# sensors_actuators_shieldv2_0.net
KiCad netlist of a schematic drawn in EAGLE
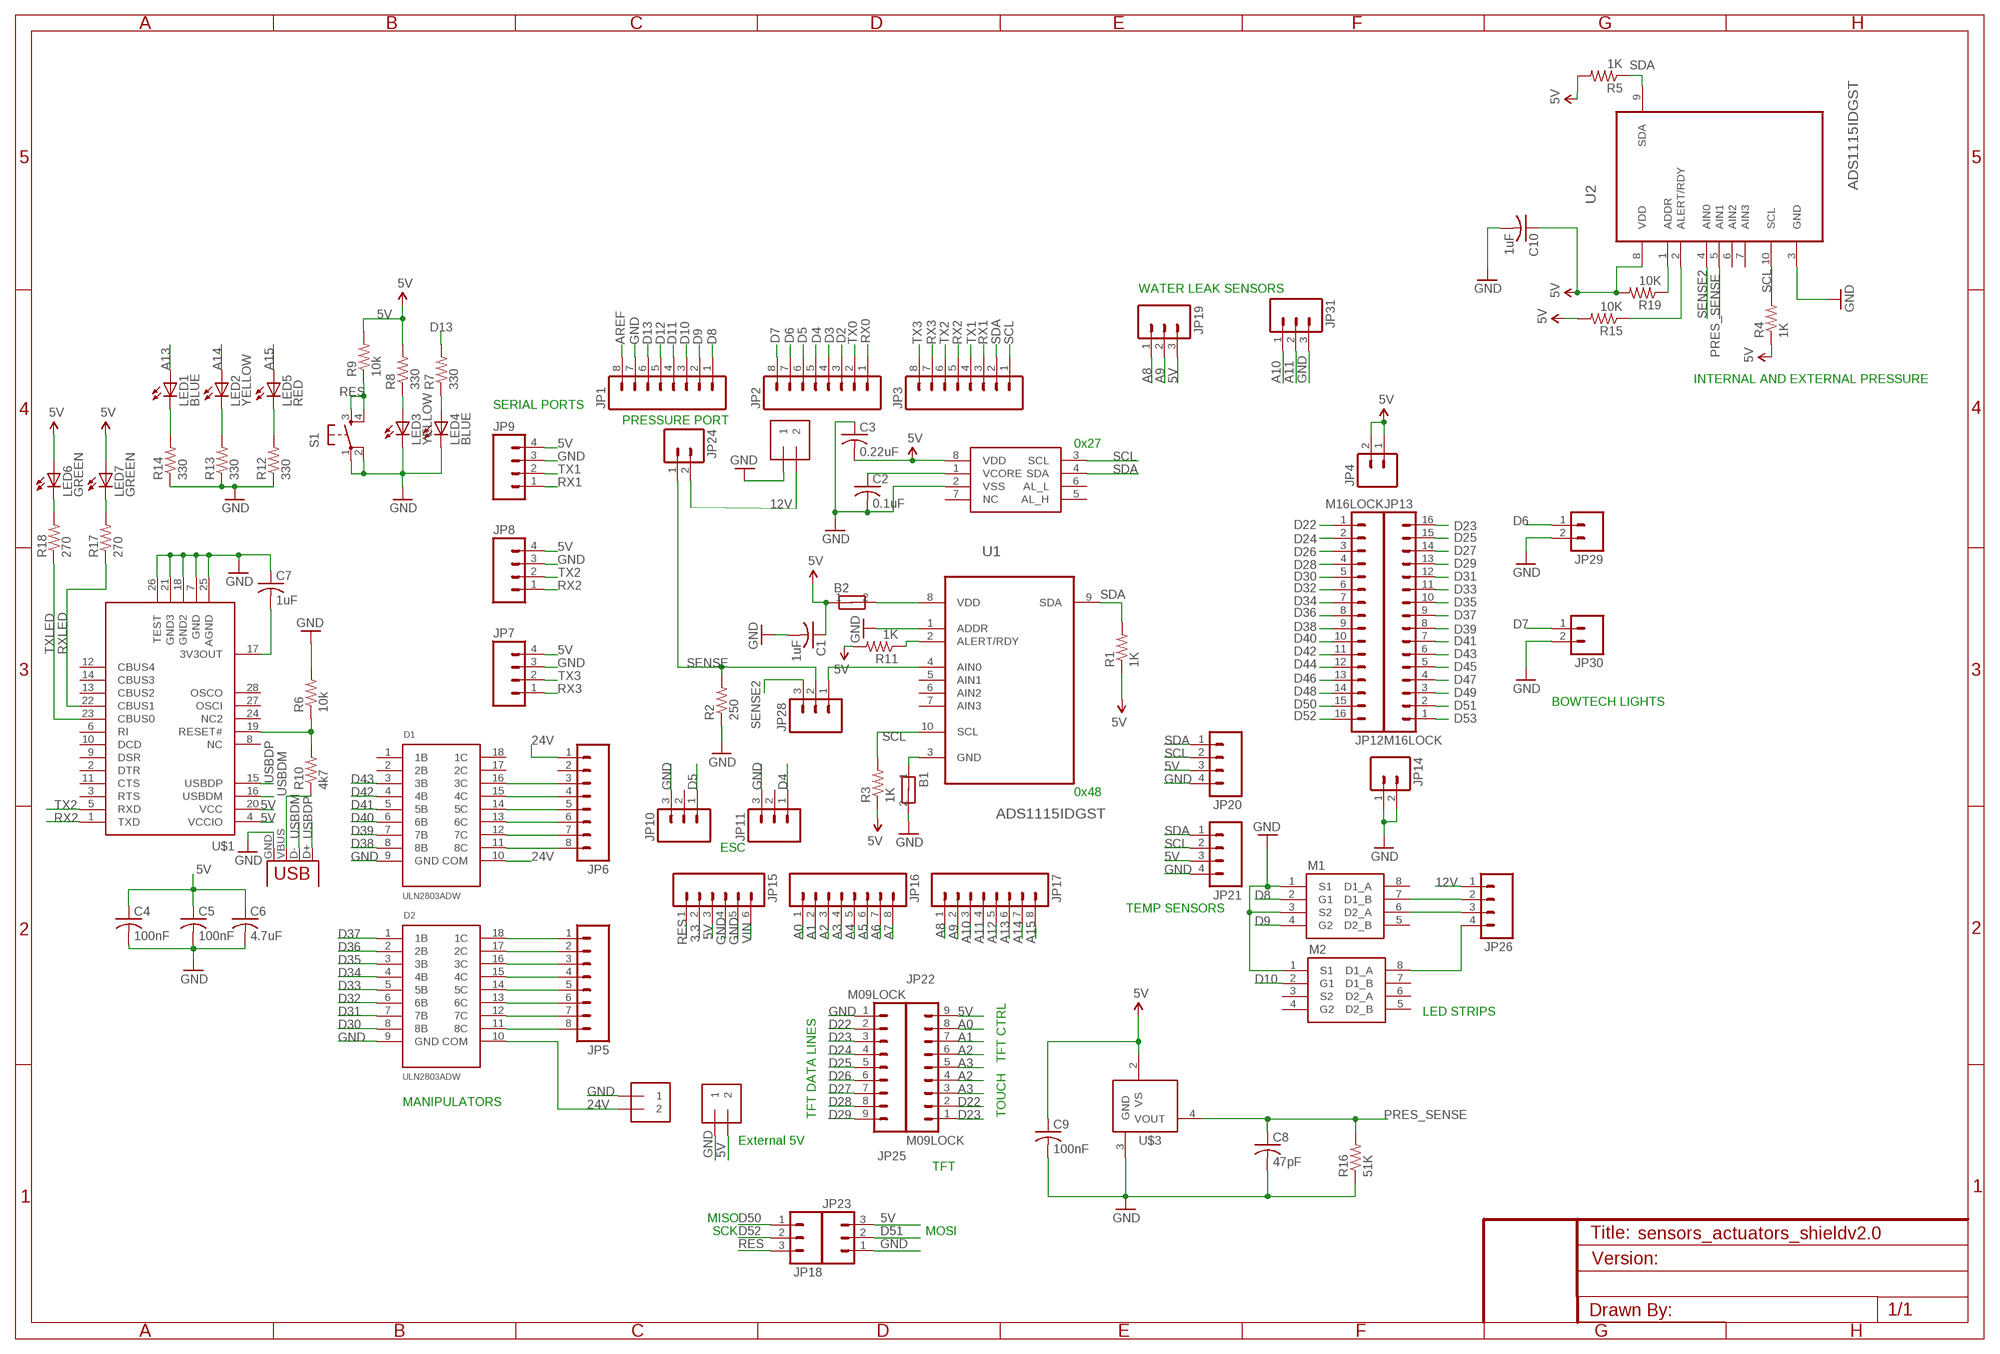
[diagram p0: schematic, sheet 1]

(export (version "E")
  (design (tool "Eeschema 10.0.6"))
  (components
    (comp (ref "B1")
      (value "MMZ2012Y152B0.4OHM,500MA")
      (footprint "eagle-import:0805")
      (fields (field (name "MPN") "MMZ2012Y152B"))
      (libsource (lib "eagle-import") (part "MMZ2012Y152B0.4OHM,500MA"))
    )
    (comp (ref "B2")
      (value "MMZ2012Y152B0.4OHM,500MA")
      (footprint "eagle-import:0805")
      (fields (field (name "MPN") "MMZ2012Y152B"))
      (libsource (lib "eagle-import") (part "MMZ2012Y152B0.4OHM,500MA"))
    )
    (comp (ref "C1")
      (value "1uF")
      (footprint "eagle-import:C0805")
      (fields (field (name "MF") "KEMET") (field (name "MPN") "C0805C105M4RACTU"))
      (libsource (lib "eagle-import") (part "C-USC0805"))
    )
    (comp (ref "C2")
      (value "0.1uF")
      (footprint "eagle-import:C0805")
      (fields (field (name "MPN") "08055C104K4Z2A"))
      (libsource (lib "eagle-import") (part "C-USC0805"))
    )
    (comp (ref "C3")
      (value "0.22uF")
      (footprint "eagle-import:C0805")
      (fields (field (name "MPN") "CGA4J2X8R1E224K125AA"))
      (libsource (lib "eagle-import") (part "C-USC0805"))
    )
    (comp (ref "C4")
      (value "100nF")
      (footprint "eagle-import:C0805")
      (fields (field (name "MPN") "MC0805B104J500CT"))
      (libsource (lib "eagle-import") (part "C-USC0805"))
    )
    (comp (ref "C5")
      (value "100nF")
      (footprint "eagle-import:C0805")
      (fields (field (name "MPN") "MC0805B104J500CT"))
      (libsource (lib "eagle-import") (part "C-USC0805"))
    )
    (comp (ref "C6")
      (value "4.7uF")
      (footprint "eagle-import:C0805")
      (fields (field (name "MPN") "C2012X5R1A475K125AA"))
      (libsource (lib "eagle-import") (part "C-USC0805"))
    )
    (comp (ref "C7")
      (value "1uF")
      (footprint "eagle-import:C0805")
      (fields (field (name "MF") "KEMET") (field (name "MPN") "C0805C105M4RACTU"))
      (libsource (lib "eagle-import") (part "C-USC0805"))
    )
    (comp (ref "C8")
      (value "47pF")
      (footprint "eagle-import:C0805")
      (fields (field (name "MF") "VISHAY/VITRAMON") (field (name "MPN") "VJ0805A470KXAMT"))
      (libsource (lib "eagle-import") (part "C-USC0805"))
    )
    (comp (ref "C9")
      (value "100nF")
      (footprint "eagle-import:C0805")
      (fields (field (name "MPN") "MC0805B104J500CT"))
      (libsource (lib "eagle-import") (part "C-USC0805"))
    )
    (comp (ref "C10")
      (value "1uF")
      (footprint "eagle-import:C0805")
      (fields (field (name "MF") "KEMET") (field (name "MPN") "C0805C105M4RACTU"))
      (libsource (lib "eagle-import") (part "C-USC0805"))
    )
    (comp (ref "D1")
      (value "ULN2803ADW")
      (footprint "eagle-import:SOIC")
      (fields (field (name "MF") "TEXAS INSTRUMENTS"))
      (libsource (lib "eagle-import") (part "ULN2803ADW"))
    )
    (comp (ref "D2")
      (value "ULN2803ADW")
      (footprint "eagle-import:SOIC")
      (fields (field (name "MF") "TEXAS INSTRUMENTS"))
      (libsource (lib "eagle-import") (part "ULN2803ADW"))
    )
    (comp (ref "J1")
      (value "1X2-3.5MM")
      (footprint "eagle-import:1X2-3.5MM")
      (fields (field (name "MPN") "691103110002"))
      (libsource (lib "eagle-import") (part "1X2-3.5MM"))
    )
    (comp (ref "J2")
      (value "1X2-3.5MM")
      (footprint "eagle-import:1X2-3.5MM")
      (fields (field (name "MPN") "691103110002"))
      (libsource (lib "eagle-import") (part "1X2-3.5MM"))
    )
    (comp (ref "J3")
      (value "1X2-3.5MM")
      (footprint "eagle-import:1X2-3.5MM")
      (fields (field (name "MPN") "691103110002"))
      (libsource (lib "eagle-import") (part "1X2-3.5MM"))
    )
    (comp (ref "JP1")
      (value "M08LOCK")
      (footprint "eagle-import:1X08_LOCK")
      (libsource (lib "eagle-import") (part "M08LOCK"))
    )
    (comp (ref "JP2")
      (value "M08LOCK")
      (footprint "eagle-import:1X08_LOCK")
      (libsource (lib "eagle-import") (part "M08LOCK"))
    )
    (comp (ref "JP3")
      (value "M08LOCK")
      (footprint "eagle-import:1X08_LOCK")
      (libsource (lib "eagle-import") (part "M08LOCK"))
    )
    (comp (ref "JP4")
      (value "M02LOCK")
      (footprint "eagle-import:1X02_LOCK")
      (libsource (lib "eagle-import") (part "M02LOCK"))
    )
    (comp (ref "JP5")
      (value "M08LOCK")
      (footprint "eagle-import:1X08_LOCK")
      (libsource (lib "eagle-import") (part "M08LOCK"))
    )
    (comp (ref "JP6")
      (value "M08LOCK")
      (footprint "eagle-import:1X08_LOCK")
      (libsource (lib "eagle-import") (part "M08LOCK"))
    )
    (comp (ref "JP7")
      (value "M04LOCK")
      (footprint "eagle-import:1X04_LOCK")
      (libsource (lib "eagle-import") (part "M04LOCK"))
    )
    (comp (ref "JP8")
      (value "M04LOCK")
      (footprint "eagle-import:1X04_LOCK")
      (libsource (lib "eagle-import") (part "M04LOCK"))
    )
    (comp (ref "JP9")
      (value "M04LOCK")
      (footprint "eagle-import:1X04_LOCK")
      (libsource (lib "eagle-import") (part "M04LOCK"))
    )
    (comp (ref "JP10")
      (value "M03LOCK")
      (footprint "eagle-import:1X03_LOCK")
      (libsource (lib "eagle-import") (part "M03LOCK"))
    )
    (comp (ref "JP11")
      (value "M03LOCK")
      (footprint "eagle-import:1X03_LOCK")
      (libsource (lib "eagle-import") (part "M03LOCK"))
    )
    (comp (ref "JP12")
      (value "M16LOCK")
      (footprint "eagle-import:1X16_LOCK")
      (libsource (lib "eagle-import") (part "M16LOCK"))
    )
    (comp (ref "JP13")
      (value "M16LOCK")
      (footprint "eagle-import:1X16_LOCK")
      (libsource (lib "eagle-import") (part "M16LOCK"))
    )
    (comp (ref "JP14")
      (value "M02LOCK")
      (footprint "eagle-import:1X02_LOCK")
      (libsource (lib "eagle-import") (part "M02LOCK"))
    )
    (comp (ref "JP15")
      (value "M06LOCK")
      (footprint "eagle-import:1X06_LOCK")
      (libsource (lib "eagle-import") (part "M06LOCK"))
    )
    (comp (ref "JP16")
      (value "M08LOCK")
      (footprint "eagle-import:1X08_LOCK")
      (libsource (lib "eagle-import") (part "M08LOCK"))
    )
    (comp (ref "JP17")
      (value "M08LOCK")
      (footprint "eagle-import:1X08_LOCK")
      (libsource (lib "eagle-import") (part "M08LOCK"))
    )
    (comp (ref "JP18")
      (value "M03LOCK")
      (footprint "eagle-import:1X03_LOCK")
      (libsource (lib "eagle-import") (part "M03LOCK"))
    )
    (comp (ref "JP19")
      (value "M03LOCK")
      (footprint "eagle-import:1X03_LOCK")
      (libsource (lib "eagle-import") (part "M03LOCK"))
    )
    (comp (ref "JP20")
      (value "M04LOCK")
      (footprint "eagle-import:1X04_LOCK")
      (libsource (lib "eagle-import") (part "M04LOCK"))
    )
    (comp (ref "JP21")
      (value "M04LOCK")
      (footprint "eagle-import:1X04_LOCK")
      (libsource (lib "eagle-import") (part "M04LOCK"))
    )
    (comp (ref "JP22")
      (value "M09LOCK")
      (footprint "eagle-import:1X09_LOCK")
      (libsource (lib "eagle-import") (part "M09LOCK"))
    )
    (comp (ref "JP23")
      (value "M03LOCK")
      (footprint "eagle-import:1X03_LOCK")
      (libsource (lib "eagle-import") (part "M03LOCK"))
    )
    (comp (ref "JP24")
      (value "M02LOCK")
      (footprint "eagle-import:1X02_LOCK")
      (libsource (lib "eagle-import") (part "M02LOCK"))
    )
    (comp (ref "JP25")
      (value "M09LOCK")
      (footprint "eagle-import:1X09_LOCK")
      (libsource (lib "eagle-import") (part "M09LOCK"))
    )
    (comp (ref "JP26")
      (value "M04LOCK")
      (footprint "eagle-import:1X04_LOCK")
      (libsource (lib "eagle-import") (part "M04LOCK"))
    )
    (comp (ref "JP27")
      (value "USBSMD")
      (footprint "eagle-import:USB-MINIB")
      (fields (field (name "MF") "MOLEX") (field (name "MPN") "67503-1020"))
      (libsource (lib "eagle-import") (part "USBSMD"))
    )
    (comp (ref "JP28")
      (value "M03LOCK")
      (footprint "eagle-import:1X03_LOCK")
      (libsource (lib "eagle-import") (part "M03LOCK"))
    )
    (comp (ref "JP29")
      (value "M02LOCK")
      (footprint "eagle-import:1X02_LOCK")
      (libsource (lib "eagle-import") (part "M02LOCK"))
    )
    (comp (ref "JP30")
      (value "M02LOCK")
      (footprint "eagle-import:1X02_LOCK")
      (libsource (lib "eagle-import") (part "M02LOCK"))
    )
    (comp (ref "JP31")
      (value "M03LOCK")
      (footprint "eagle-import:1X03_LOCK")
      (libsource (lib "eagle-import") (part "M03LOCK"))
    )
    (comp (ref "LED1")
      (value "BLUE")
      (footprint "eagle-import:CHIPLED_0805")
      (fields (field (name "MPN") "150080BS75000"))
      (libsource (lib "eagle-import") (part "LEDCHIPLED_0805"))
    )
    (comp (ref "LED2")
      (value "YELLOW")
      (footprint "eagle-import:CHIPLED_0805")
      (fields (field (name "MPN") "KP-2012SYCK-J3"))
      (libsource (lib "eagle-import") (part "LEDCHIPLED_0805"))
    )
    (comp (ref "LED3")
      (value "YELLOW")
      (footprint "eagle-import:CHIPLED_0805")
      (fields (field (name "MPN") "KP-2012SYCK-J3"))
      (libsource (lib "eagle-import") (part "LEDCHIPLED_0805"))
    )
    (comp (ref "LED4")
      (value "BLUE")
      (footprint "eagle-import:CHIPLED_0805")
      (fields (field (name "MPN") "150080BS75000"))
      (libsource (lib "eagle-import") (part "LEDCHIPLED_0805"))
    )
    (comp (ref "LED5")
      (value "RED")
      (footprint "eagle-import:CHIPLED_0805")
      (fields (field (name "MPN") "OVS-0808"))
      (libsource (lib "eagle-import") (part "LEDCHIPLED_0805"))
    )
    (comp (ref "LED6")
      (value "GREEN")
      (footprint "eagle-import:CHIPLED_0805")
      (fields (field (name "MF") "SLI (CML/IDI)") (field (name "MPN") "CMD17-21VGC/TR8"))
      (libsource (lib "eagle-import") (part "LEDCHIPLED_0805"))
    )
    (comp (ref "LED7")
      (value "GREEN")
      (footprint "eagle-import:CHIPLED_0805")
      (fields (field (name "MF") "SLI (CML/IDI)") (field (name "MPN") "CMD17-21VGC/TR8"))
      (libsource (lib "eagle-import") (part "LEDCHIPLED_0805"))
    )
    (comp (ref "M1")
      (value "IRF7910PBF")
      (footprint "eagle-import:SO-8")
      (libsource (lib "eagle-import") (part "IRF7910PBF"))
    )
    (comp (ref "M2")
      (value "IRF7910PBF")
      (footprint "eagle-import:SO-8")
      (libsource (lib "eagle-import") (part "IRF7910PBF"))
    )
    (comp (ref "R1")
      (value "1K")
      (footprint "eagle-import:M0805")
      (fields (field (name "MF") "VISHAY/DALE") (field (name "MPN") "CRCW08051K00FKTA"))
      (libsource (lib "eagle-import") (part "R-US_M0805"))
    )
    (comp (ref "R2")
      (value "250")
      (footprint "eagle-import:M0805")
      (fields (field (name "MPN") "PLTT0805Z2500AGTS"))
      (libsource (lib "eagle-import") (part "R-US_M0805"))
    )
    (comp (ref "R3")
      (value "1K")
      (footprint "eagle-import:M0805")
      (fields (field (name "MF") "VISHAY/DALE") (field (name "MPN") "CRCW08051K00FKTA"))
      (libsource (lib "eagle-import") (part "R-US_M0805"))
    )
    (comp (ref "R4")
      (value "1K")
      (footprint "eagle-import:M0805")
      (fields (field (name "MF") "VISHAY/DALE") (field (name "MPN") "CRCW08051K00FKTA"))
      (libsource (lib "eagle-import") (part "R-US_M0805"))
    )
    (comp (ref "R5")
      (value "1K")
      (footprint "eagle-import:M0805")
      (fields (field (name "MF") "VISHAY/DALE") (field (name "MPN") "CRCW08051K00FKTA"))
      (libsource (lib "eagle-import") (part "R-US_M0805"))
    )
    (comp (ref "R6")
      (value "10k")
      (footprint "eagle-import:M0805")
      (fields (field (name "MPN") "MCHP05W4F1002T5E"))
      (libsource (lib "eagle-import") (part "R-US_M0805"))
    )
    (comp (ref "R7")
      (value "330")
      (footprint "eagle-import:M0805")
      (fields (field (name "MPN") "MCHP05W4F3300T5E"))
      (libsource (lib "eagle-import") (part "R-US_M0805"))
    )
    (comp (ref "R8")
      (value "330")
      (footprint "eagle-import:M0805")
      (fields (field (name "MPN") "MCHP05W4F3300T5E"))
      (libsource (lib "eagle-import") (part "R-US_M0805"))
    )
    (comp (ref "R9")
      (value "10k")
      (footprint "eagle-import:M0805")
      (fields (field (name "MPN") "MCHP05W4F1002T5E"))
      (libsource (lib "eagle-import") (part "R-US_M0805"))
    )
    (comp (ref "R10")
      (value "4k7")
      (footprint "eagle-import:M0805")
      (fields (field (name "MPN") "CR0805-JW-472ELF"))
      (libsource (lib "eagle-import") (part "R-US_M0805"))
    )
    (comp (ref "R11")
      (value "1K")
      (footprint "eagle-import:M0805")
      (fields (field (name "MF") "VISHAY/DALE") (field (name "MPN") "CRCW08051K00FKTA"))
      (libsource (lib "eagle-import") (part "R-US_M0805"))
    )
    (comp (ref "R12")
      (value "330")
      (footprint "eagle-import:M0805")
      (fields (field (name "MPN") "MCHP05W4F3300T5E"))
      (libsource (lib "eagle-import") (part "R-US_M0805"))
    )
    (comp (ref "R13")
      (value "330")
      (footprint "eagle-import:M0805")
      (fields (field (name "MPN") "MCHP05W4F3300T5E"))
      (libsource (lib "eagle-import") (part "R-US_M0805"))
    )
    (comp (ref "R14")
      (value "330")
      (footprint "eagle-import:M0805")
      (fields (field (name "MPN") "MCHP05W4F3300T5E"))
      (libsource (lib "eagle-import") (part "R-US_M0805"))
    )
    (comp (ref "R15")
      (value "10K")
      (footprint "eagle-import:M0805")
      (libsource (lib "eagle-import") (part "R-US_M0805"))
    )
    (comp (ref "R16")
      (value "51K")
      (footprint "eagle-import:M0805")
      (fields (field (name "MF") "OUTSOURCE ITEM") (field (name "MPN") "RR1220P-513-B-T5"))
      (libsource (lib "eagle-import") (part "R-US_M0805"))
    )
    (comp (ref "R17")
      (value "270")
      (footprint "eagle-import:M0805")
      (fields (field (name "MPN") "MC0805S8F2700T5E"))
      (libsource (lib "eagle-import") (part "R-US_M0805"))
    )
    (comp (ref "R18")
      (value "270")
      (footprint "eagle-import:M0805")
      (fields (field (name "MPN") "MC0805S8F2700T5E"))
      (libsource (lib "eagle-import") (part "R-US_M0805"))
    )
    (comp (ref "R19")
      (value "10K")
      (footprint "eagle-import:M0805")
      (libsource (lib "eagle-import") (part "R-US_M0805"))
    )
    (comp (ref "S1")
      (value "TAC_SWITCHPTH")
      (footprint "eagle-import:TACTILE-PTH")
      (libsource (lib "eagle-import") (part "TAC_SWITCHPTH"))
    )
    (comp (ref "U$1")
      (value "FT232RL")
      (footprint "eagle-import:SSOP-28")
      (libsource (lib "eagle-import") (part "FT232RL"))
    )
    (comp (ref "U$2")
      (value "HIH6130")
      (footprint "eagle-import:SO-8")
      (fields (field (name "MPN") "HIH6131-021-001"))
      (libsource (lib "eagle-import") (part "HIH6130"))
    )
    (comp (ref "U$3")
      (value "MPXH6250A")
      (footprint "eagle-import:SSOP-8")
      (libsource (lib "eagle-import") (part "MPXH6250A"))
    )
    (comp (ref "U1")
      (value "ADS1115IDGST")
      (footprint "eagle-import:SOP50P490X110-10N")
      (libsource (lib "eagle-import") (part "ADS1115IDGST"))
    )
    (comp (ref "U2")
      (value "ADS1115IDGST")
      (footprint "eagle-import:SOP50P490X110-10N")
      (libsource (lib "eagle-import") (part "ADS1115IDGST"))
    )
  )
  (nets
    (net (code "1") (name "/3.3") (class "Default")
      (node (ref "JP15") (pin "2") (pinfunction "2_2") (pintype "passive"))
    )
    (net (code "2") (name "/12V") (class "Default")
      (node (ref "J1") (pin "2") (pinfunction "2_2") (pintype "passive"))
      (node (ref "JP24") (pin "2") (pinfunction "2_2") (pintype "passive"))
      (node (ref "JP26") (pin "1") (pinfunction "1_1") (pintype "passive"))
    )
    (net (code "3") (name "/24V") (class "Default")
      (node (ref "D1") (pin "10") (pinfunction "COM_10") (pintype "bidirectional"))
      (node (ref "D2") (pin "10") (pinfunction "COM_10") (pintype "bidirectional"))
      (node (ref "J2") (pin "2") (pinfunction "2_2") (pintype "passive"))
      (node (ref "JP6") (pin "1") (pinfunction "1_1") (pintype "passive"))
    )
    (net (code "4") (name "/A0") (class "Default")
      (node (ref "JP16") (pin "1") (pinfunction "1_1") (pintype "passive"))
      (node (ref "JP22") (pin "8") (pinfunction "8_8") (pintype "passive"))
    )
    (net (code "5") (name "/A1") (class "Default")
      (node (ref "JP16") (pin "2") (pinfunction "2_2") (pintype "passive"))
      (node (ref "JP22") (pin "7") (pinfunction "7_7") (pintype "passive"))
    )
    (net (code "6") (name "/A2") (class "Default")
      (node (ref "JP16") (pin "3") (pinfunction "3_3") (pintype "passive"))
      (node (ref "JP22") (pin "4") (pinfunction "4_4") (pintype "passive"))
      (node (ref "JP22") (pin "6") (pinfunction "6_6") (pintype "passive"))
    )
    (net (code "7") (name "/A3") (class "Default")
      (node (ref "JP16") (pin "4") (pinfunction "4_4") (pintype "passive"))
      (node (ref "JP22") (pin "3") (pinfunction "3_3") (pintype "passive"))
      (node (ref "JP22") (pin "5") (pinfunction "5_5") (pintype "passive"))
    )
    (net (code "8") (name "/A4") (class "Default")
      (node (ref "JP16") (pin "5") (pinfunction "5_5") (pintype "passive"))
    )
    (net (code "9") (name "/A5") (class "Default")
      (node (ref "JP16") (pin "6") (pinfunction "6_6") (pintype "passive"))
    )
    (net (code "10") (name "/A6") (class "Default")
      (node (ref "JP16") (pin "7") (pinfunction "7_7") (pintype "passive"))
    )
    (net (code "11") (name "/A7") (class "Default")
      (node (ref "JP16") (pin "8") (pinfunction "8_8") (pintype "passive"))
    )
    (net (code "12") (name "/A8") (class "Default")
      (node (ref "JP17") (pin "1") (pinfunction "1_1") (pintype "passive"))
      (node (ref "JP19") (pin "1") (pinfunction "1_1") (pintype "passive"))
    )
    (net (code "13") (name "/A9") (class "Default")
      (node (ref "JP17") (pin "2") (pinfunction "2_2") (pintype "passive"))
      (node (ref "JP19") (pin "2") (pinfunction "2_2") (pintype "passive"))
    )
    (net (code "14") (name "/A10") (class "Default")
      (node (ref "JP17") (pin "3") (pinfunction "3_3") (pintype "passive"))
      (node (ref "JP31") (pin "1") (pinfunction "1_1") (pintype "passive"))
    )
    (net (code "15") (name "/A11") (class "Default")
      (node (ref "JP17") (pin "4") (pinfunction "4_4") (pintype "passive"))
      (node (ref "JP31") (pin "2") (pinfunction "2_2") (pintype "passive"))
    )
    (net (code "16") (name "/A12") (class "Default")
      (node (ref "JP17") (pin "5") (pinfunction "5_5") (pintype "passive"))
    )
    (net (code "17") (name "/A13") (class "Default")
      (node (ref "JP17") (pin "6") (pinfunction "6_6") (pintype "passive"))
      (node (ref "LED1") (pin "A") (pinfunction "A_A") (pintype "passive"))
    )
    (net (code "18") (name "/A14") (class "Default")
      (node (ref "JP17") (pin "7") (pinfunction "7_7") (pintype "passive"))
      (node (ref "LED2") (pin "A") (pinfunction "A_A") (pintype "passive"))
    )
    (net (code "19") (name "/A15") (class "Default")
      (node (ref "JP17") (pin "8") (pinfunction "8_8") (pintype "passive"))
      (node (ref "LED5") (pin "A") (pinfunction "A_A") (pintype "passive"))
    )
    (net (code "20") (name "/AREF") (class "Default")
      (node (ref "JP1") (pin "8") (pinfunction "8_8") (pintype "passive"))
    )
    (net (code "21") (name "/D2") (class "Default")
      (node (ref "JP2") (pin "3") (pinfunction "3_3") (pintype "passive"))
    )
    (net (code "22") (name "/D3") (class "Default")
      (node (ref "JP2") (pin "4") (pinfunction "4_4") (pintype "passive"))
    )
    (net (code "23") (name "/D4") (class "Default")
      (node (ref "JP11") (pin "1") (pinfunction "1_1") (pintype "passive"))
      (node (ref "JP2") (pin "5") (pinfunction "5_5") (pintype "passive"))
    )
    (net (code "24") (name "/D5") (class "Default")
      (node (ref "JP10") (pin "1") (pinfunction "1_1") (pintype "passive"))
      (node (ref "JP2") (pin "6") (pinfunction "6_6") (pintype "passive"))
    )
    (net (code "25") (name "/D6") (class "Default")
      (node (ref "JP2") (pin "7") (pinfunction "7_7") (pintype "passive"))
      (node (ref "JP29") (pin "1") (pinfunction "1_1") (pintype "passive"))
    )
    (net (code "26") (name "/D7") (class "Default")
      (node (ref "JP2") (pin "8") (pinfunction "8_8") (pintype "passive"))
      (node (ref "JP30") (pin "1") (pinfunction "1_1") (pintype "passive"))
    )
    (net (code "27") (name "/D8") (class "Default")
      (node (ref "JP1") (pin "1") (pinfunction "1_1") (pintype "passive"))
      (node (ref "M1") (pin "2") (pinfunction "G1_2") (pintype "bidirectional"))
    )
    (net (code "28") (name "/D9") (class "Default")
      (node (ref "JP1") (pin "2") (pinfunction "2_2") (pintype "passive"))
      (node (ref "M1") (pin "4") (pinfunction "G2_4") (pintype "bidirectional"))
    )
    (net (code "29") (name "/D10") (class "Default")
      (node (ref "JP1") (pin "3") (pinfunction "3_3") (pintype "passive"))
      (node (ref "M2") (pin "2") (pinfunction "G1_2") (pintype "bidirectional"))
    )
    (net (code "30") (name "/D11") (class "Default")
      (node (ref "JP1") (pin "4") (pinfunction "4_4") (pintype "passive"))
    )
    (net (code "31") (name "/D12") (class "Default")
      (node (ref "JP1") (pin "5") (pinfunction "5_5") (pintype "passive"))
    )
    (net (code "32") (name "/D13") (class "Default")
      (node (ref "JP1") (pin "6") (pinfunction "6_6") (pintype "passive"))
      (node (ref "R7") (pin "2") (pinfunction "2_2") (pintype "passive"))
    )
    (net (code "33") (name "/D22") (class "Default")
      (node (ref "JP12") (pin "1") (pinfunction "1_1") (pintype "passive"))
      (node (ref "JP22") (pin "2") (pinfunction "2_2") (pintype "passive"))
      (node (ref "JP25") (pin "2") (pinfunction "2_2") (pintype "passive"))
    )
    (net (code "34") (name "/D23") (class "Default")
      (node (ref "JP13") (pin "16") (pinfunction "16_16") (pintype "passive"))
      (node (ref "JP22") (pin "1") (pinfunction "1_1") (pintype "passive"))
      (node (ref "JP25") (pin "3") (pinfunction "3_3") (pintype "passive"))
    )
    (net (code "35") (name "/D24") (class "Default")
      (node (ref "JP12") (pin "2") (pinfunction "2_2") (pintype "passive"))
      (node (ref "JP25") (pin "4") (pinfunction "4_4") (pintype "passive"))
    )
    (net (code "36") (name "/D25") (class "Default")
      (node (ref "JP13") (pin "15") (pinfunction "15_15") (pintype "passive"))
      (node (ref "JP25") (pin "5") (pinfunction "5_5") (pintype "passive"))
    )
    (net (code "37") (name "/D26") (class "Default")
      (node (ref "JP12") (pin "3") (pinfunction "3_3") (pintype "passive"))
      (node (ref "JP25") (pin "6") (pinfunction "6_6") (pintype "passive"))
    )
    (net (code "38") (name "/D27") (class "Default")
      (node (ref "JP13") (pin "14") (pinfunction "14_14") (pintype "passive"))
      (node (ref "JP25") (pin "7") (pinfunction "7_7") (pintype "passive"))
    )
    (net (code "39") (name "/D28") (class "Default")
      (node (ref "JP12") (pin "4") (pinfunction "4_4") (pintype "passive"))
      (node (ref "JP25") (pin "8") (pinfunction "8_8") (pintype "passive"))
    )
    (net (code "40") (name "/D29") (class "Default")
      (node (ref "JP13") (pin "13") (pinfunction "13_13") (pintype "passive"))
      (node (ref "JP25") (pin "9") (pinfunction "9_9") (pintype "passive"))
    )
    (net (code "41") (name "/D30") (class "Default")
      (node (ref "D2") (pin "8") (pinfunction "8B_8") (pintype "bidirectional"))
      (node (ref "JP12") (pin "5") (pinfunction "5_5") (pintype "passive"))
    )
    (net (code "42") (name "/D31") (class "Default")
      (node (ref "D2") (pin "7") (pinfunction "7B_7") (pintype "bidirectional"))
      (node (ref "JP13") (pin "12") (pinfunction "12_12") (pintype "passive"))
    )
    (net (code "43") (name "/D32") (class "Default")
      (node (ref "D2") (pin "6") (pinfunction "6B_6") (pintype "bidirectional"))
      (node (ref "JP12") (pin "6") (pinfunction "6_6") (pintype "passive"))
    )
    (net (code "44") (name "/D33") (class "Default")
      (node (ref "D2") (pin "5") (pinfunction "5B_5") (pintype "bidirectional"))
      (node (ref "JP13") (pin "11") (pinfunction "11_11") (pintype "passive"))
    )
    (net (code "45") (name "/D34") (class "Default")
      (node (ref "D2") (pin "4") (pinfunction "4B_4") (pintype "bidirectional"))
      (node (ref "JP12") (pin "7") (pinfunction "7_7") (pintype "passive"))
    )
    (net (code "46") (name "/D35") (class "Default")
      (node (ref "D2") (pin "3") (pinfunction "3B_3") (pintype "bidirectional"))
      (node (ref "JP13") (pin "10") (pinfunction "10_10") (pintype "passive"))
    )
    (net (code "47") (name "/D36") (class "Default")
      (node (ref "D2") (pin "2") (pinfunction "2B_2") (pintype "bidirectional"))
      (node (ref "JP12") (pin "8") (pinfunction "8_8") (pintype "passive"))
    )
    (net (code "48") (name "/D37") (class "Default")
      (node (ref "D2") (pin "1") (pinfunction "1B_1") (pintype "bidirectional"))
      (node (ref "JP13") (pin "9") (pinfunction "9_9") (pintype "passive"))
    )
    (net (code "49") (name "/D38") (class "Default")
      (node (ref "D1") (pin "8") (pinfunction "8B_8") (pintype "bidirectional"))
      (node (ref "JP12") (pin "9") (pinfunction "9_9") (pintype "passive"))
    )
    (net (code "50") (name "/D39") (class "Default")
      (node (ref "D1") (pin "7") (pinfunction "7B_7") (pintype "bidirectional"))
      (node (ref "JP13") (pin "8") (pinfunction "8_8") (pintype "passive"))
    )
    (net (code "51") (name "/D40") (class "Default")
      (node (ref "D1") (pin "6") (pinfunction "6B_6") (pintype "bidirectional"))
      (node (ref "JP12") (pin "10") (pinfunction "10_10") (pintype "passive"))
    )
    (net (code "52") (name "/D41") (class "Default")
      (node (ref "D1") (pin "5") (pinfunction "5B_5") (pintype "bidirectional"))
      (node (ref "JP13") (pin "7") (pinfunction "7_7") (pintype "passive"))
    )
    (net (code "53") (name "/D42") (class "Default")
      (node (ref "D1") (pin "4") (pinfunction "4B_4") (pintype "bidirectional"))
      (node (ref "JP12") (pin "11") (pinfunction "11_11") (pintype "passive"))
    )
    (net (code "54") (name "/D43") (class "Default")
      (node (ref "D1") (pin "3") (pinfunction "3B_3") (pintype "bidirectional"))
      (node (ref "JP13") (pin "6") (pinfunction "6_6") (pintype "passive"))
    )
    (net (code "55") (name "/D44") (class "Default")
      (node (ref "JP12") (pin "12") (pinfunction "12_12") (pintype "passive"))
    )
    (net (code "56") (name "/D45") (class "Default")
      (node (ref "JP13") (pin "5") (pinfunction "5_5") (pintype "passive"))
    )
    (net (code "57") (name "/D46") (class "Default")
      (node (ref "JP12") (pin "13") (pinfunction "13_13") (pintype "passive"))
    )
    (net (code "58") (name "/D47") (class "Default")
      (node (ref "JP13") (pin "4") (pinfunction "4_4") (pintype "passive"))
    )
    (net (code "59") (name "/D48") (class "Default")
      (node (ref "JP12") (pin "14") (pinfunction "14_14") (pintype "passive"))
    )
    (net (code "60") (name "/D49") (class "Default")
      (node (ref "JP13") (pin "3") (pinfunction "3_3") (pintype "passive"))
    )
    (net (code "61") (name "/D50") (class "Default")
      (node (ref "JP12") (pin "15") (pinfunction "15_15") (pintype "passive"))
      (node (ref "JP18") (pin "1") (pinfunction "1_1") (pintype "passive"))
    )
    (net (code "62") (name "/D51") (class "Default")
      (node (ref "JP13") (pin "2") (pinfunction "2_2") (pintype "passive"))
      (node (ref "JP23") (pin "2") (pinfunction "2_2") (pintype "passive"))
    )
    (net (code "63") (name "/D52") (class "Default")
      (node (ref "JP12") (pin "16") (pinfunction "16_16") (pintype "passive"))
      (node (ref "JP18") (pin "2") (pinfunction "2_2") (pintype "passive"))
    )
    (net (code "64") (name "/D53") (class "Default")
      (node (ref "JP13") (pin "1") (pinfunction "1_1") (pintype "passive"))
    )
    (net (code "65") (name "/PRES_SENSE") (class "Default")
      (node (ref "C8") (pin "1") (pinfunction "1_1") (pintype "passive"))
      (node (ref "R16") (pin "2") (pinfunction "2_2") (pintype "passive"))
      (node (ref "U$3") (pin "4") (pinfunction "VOUT_4") (pintype "bidirectional"))
      (node (ref "U2") (pin "5") (pinfunction "AIN1_5") (pintype "input"))
    )
    (net (code "66") (name "/RES") (class "Default")
      (node (ref "JP15") (pin "1") (pinfunction "1_1") (pintype "passive"))
      (node (ref "JP18") (pin "3") (pinfunction "3_3") (pintype "passive"))
      (node (ref "R9") (pin "1") (pinfunction "1_1") (pintype "passive"))
      (node (ref "S1") (pin "3") (pinfunction "3_3") (pintype "passive"))
      (node (ref "S1") (pin "4") (pinfunction "4_4") (pintype "passive"))
    )
    (net (code "67") (name "/RX0") (class "Default")
      (node (ref "JP2") (pin "1") (pinfunction "1_1") (pintype "passive"))
    )
    (net (code "68") (name "/RX1") (class "Default")
      (node (ref "JP3") (pin "3") (pinfunction "3_3") (pintype "passive"))
      (node (ref "JP9") (pin "1") (pinfunction "1_1") (pintype "passive"))
    )
    (net (code "69") (name "/RX2") (class "Default")
      (node (ref "JP3") (pin "5") (pinfunction "5_5") (pintype "passive"))
      (node (ref "JP8") (pin "1") (pinfunction "1_1") (pintype "passive"))
      (node (ref "U$1") (pin "1") (pinfunction "TXD_1") (pintype "bidirectional"))
    )
    (net (code "70") (name "/RX3") (class "Default")
      (node (ref "JP3") (pin "7") (pinfunction "7_7") (pintype "passive"))
      (node (ref "JP7") (pin "1") (pinfunction "1_1") (pintype "passive"))
    )
    (net (code "71") (name "/RXLED") (class "Default")
      (node (ref "R17") (pin "1") (pinfunction "1_1") (pintype "passive"))
      (node (ref "U$1") (pin "22") (pinfunction "CBUS1_22") (pintype "bidirectional"))
    )
    (net (code "72") (name "/SCL") (class "Default")
      (node (ref "JP20") (pin "2") (pinfunction "2_2") (pintype "passive"))
      (node (ref "JP21") (pin "2") (pinfunction "2_2") (pintype "passive"))
      (node (ref "JP3") (pin "1") (pinfunction "1_1") (pintype "passive"))
      (node (ref "R3") (pin "2") (pinfunction "2_2") (pintype "passive"))
      (node (ref "R4") (pin "2") (pinfunction "2_2") (pintype "passive"))
      (node (ref "U$2") (pin "3") (pinfunction "SCL_3") (pintype "bidirectional"))
      (node (ref "U1") (pin "10") (pinfunction "SCL_10") (pintype "input"))
      (node (ref "U2") (pin "10") (pinfunction "SCL_10") (pintype "input"))
    )
    (net (code "73") (name "/SDA") (class "Default")
      (node (ref "JP20") (pin "1") (pinfunction "1_1") (pintype "passive"))
      (node (ref "JP21") (pin "1") (pinfunction "1_1") (pintype "passive"))
      (node (ref "JP3") (pin "2") (pinfunction "2_2") (pintype "passive"))
      (node (ref "R1") (pin "2") (pinfunction "2_2") (pintype "passive"))
      (node (ref "R5") (pin "1") (pinfunction "1_1") (pintype "passive"))
      (node (ref "U$2") (pin "4") (pinfunction "SDA_4") (pintype "bidirectional"))
      (node (ref "U1") (pin "9") (pinfunction "SDA_9") (pintype "bidirectional"))
      (node (ref "U2") (pin "9") (pinfunction "SDA_9") (pintype "bidirectional"))
    )
    (net (code "74") (name "/SENSE") (class "Default")
      (node (ref "JP24") (pin "1") (pinfunction "1_1") (pintype "passive"))
      (node (ref "JP28") (pin "2") (pinfunction "2_2") (pintype "passive"))
      (node (ref "R2") (pin "2") (pinfunction "2_2") (pintype "passive"))
    )
    (net (code "75") (name "/SENSE2") (class "Default")
      (node (ref "JP28") (pin "3") (pinfunction "3_3") (pintype "passive"))
      (node (ref "U2") (pin "4") (pinfunction "AIN0_4") (pintype "input"))
    )
    (net (code "76") (name "/TX0") (class "Default")
      (node (ref "JP2") (pin "2") (pinfunction "2_2") (pintype "passive"))
    )
    (net (code "77") (name "/TX1") (class "Default")
      (node (ref "JP3") (pin "4") (pinfunction "4_4") (pintype "passive"))
      (node (ref "JP9") (pin "2") (pinfunction "2_2") (pintype "passive"))
    )
    (net (code "78") (name "/TX2") (class "Default")
      (node (ref "JP3") (pin "6") (pinfunction "6_6") (pintype "passive"))
      (node (ref "JP8") (pin "2") (pinfunction "2_2") (pintype "passive"))
      (node (ref "U$1") (pin "5") (pinfunction "RXD_5") (pintype "bidirectional"))
    )
    (net (code "79") (name "/TX3") (class "Default")
      (node (ref "JP3") (pin "8") (pinfunction "8_8") (pintype "passive"))
      (node (ref "JP7") (pin "2") (pinfunction "2_2") (pintype "passive"))
    )
    (net (code "80") (name "/TXLED") (class "Default")
      (node (ref "R18") (pin "1") (pinfunction "1_1") (pintype "passive"))
      (node (ref "U$1") (pin "23") (pinfunction "CBUS0_23") (pintype "bidirectional"))
    )
    (net (code "81") (name "/USBDM") (class "Default")
      (node (ref "JP27") (pin "D-") (pinfunction "D-_D-") (pintype "bidirectional"))
      (node (ref "U$1") (pin "16") (pinfunction "USBDM_16") (pintype "bidirectional"))
    )
    (net (code "82") (name "/USBDP") (class "Default")
      (node (ref "JP27") (pin "D+") (pinfunction "D+_D+") (pintype "bidirectional"))
      (node (ref "U$1") (pin "15") (pinfunction "USBDP_15") (pintype "bidirectional"))
    )
    (net (code "83") (name "/VIN") (class "Default")
      (node (ref "JP15") (pin "6") (pinfunction "6_6") (pintype "passive"))
    )
    (net (code "84") (name "5V") (class "Default")
      (node (ref "B2") (pin "1") (pinfunction "1_1") (pintype "passive"))
      (node (ref "C1") (pin "1") (pinfunction "1_1") (pintype "passive"))
      (node (ref "C10") (pin "1") (pinfunction "1_1") (pintype "passive"))
      (node (ref "C3") (pin "2") (pinfunction "2_2") (pintype "passive"))
      (node (ref "C4") (pin "1") (pinfunction "1_1") (pintype "passive"))
      (node (ref "C5") (pin "1") (pinfunction "1_1") (pintype "passive"))
      (node (ref "C6") (pin "1") (pinfunction "1_1") (pintype "passive"))
      (node (ref "C9") (pin "1") (pinfunction "1_1") (pintype "passive"))
      (node (ref "J3") (pin "2") (pinfunction "2_2") (pintype "passive"))
      (node (ref "JP15") (pin "3") (pinfunction "3_3") (pintype "passive"))
      (node (ref "JP19") (pin "3") (pinfunction "3_3") (pintype "passive"))
      (node (ref "JP20") (pin "3") (pinfunction "3_3") (pintype "passive"))
      (node (ref "JP21") (pin "3") (pinfunction "3_3") (pintype "passive"))
      (node (ref "JP22") (pin "9") (pinfunction "9_9") (pintype "passive"))
      (node (ref "JP23") (pin "3") (pinfunction "3_3") (pintype "passive"))
      (node (ref "JP4") (pin "1") (pinfunction "1_1") (pintype "passive"))
      (node (ref "JP4") (pin "2") (pinfunction "2_2") (pintype "passive"))
      (node (ref "JP7") (pin "4") (pinfunction "4_4") (pintype "passive"))
      (node (ref "JP8") (pin "4") (pinfunction "4_4") (pintype "passive"))
      (node (ref "JP9") (pin "4") (pinfunction "4_4") (pintype "passive"))
      (node (ref "LED6") (pin "A") (pinfunction "A_A") (pintype "passive"))
      (node (ref "LED7") (pin "A") (pinfunction "A_A") (pintype "passive"))
      (node (ref "R1") (pin "1") (pinfunction "1_1") (pintype "passive"))
      (node (ref "R11") (pin "2") (pinfunction "2_2") (pintype "passive"))
      (node (ref "R15") (pin "2") (pinfunction "2_2") (pintype "passive"))
      (node (ref "R19") (pin "2") (pinfunction "2_2") (pintype "passive"))
      (node (ref "R3") (pin "1") (pinfunction "1_1") (pintype "passive"))
      (node (ref "R4") (pin "1") (pinfunction "1_1") (pintype "passive"))
      (node (ref "R5") (pin "2") (pinfunction "2_2") (pintype "passive"))
      (node (ref "R8") (pin "2") (pinfunction "2_2") (pintype "passive"))
      (node (ref "R9") (pin "2") (pinfunction "2_2") (pintype "passive"))
      (node (ref "U$1") (pin "20") (pinfunction "VCC_20") (pintype "bidirectional"))
      (node (ref "U$1") (pin "4") (pinfunction "VCCIO_4") (pintype "bidirectional"))
      (node (ref "U$2") (pin "8") (pinfunction "VDD_8") (pintype "bidirectional"))
      (node (ref "U$3") (pin "2") (pinfunction "VS_2") (pintype "bidirectional"))
      (node (ref "U2") (pin "8") (pinfunction "VDD_8") (pintype "power_in"))
    )
    (net (code "85") (name "GND") (class "Default")
      (node (ref "B1") (pin "2") (pinfunction "2_2") (pintype "passive"))
      (node (ref "C1") (pin "2") (pinfunction "2_2") (pintype "passive"))
      (node (ref "C10") (pin "2") (pinfunction "2_2") (pintype "passive"))
      (node (ref "C2") (pin "2") (pinfunction "2_2") (pintype "passive"))
      (node (ref "C3") (pin "1") (pinfunction "1_1") (pintype "passive"))
      (node (ref "C4") (pin "2") (pinfunction "2_2") (pintype "passive"))
      (node (ref "C5") (pin "2") (pinfunction "2_2") (pintype "passive"))
      (node (ref "C6") (pin "2") (pinfunction "2_2") (pintype "passive"))
      (node (ref "C7") (pin "1") (pinfunction "1_1") (pintype "passive"))
      (node (ref "C8") (pin "2") (pinfunction "2_2") (pintype "passive"))
      (node (ref "C9") (pin "2") (pinfunction "2_2") (pintype "passive"))
      (node (ref "D1") (pin "9") (pinfunction "GND_9") (pintype "bidirectional"))
      (node (ref "D2") (pin "9") (pinfunction "GND_9") (pintype "bidirectional"))
      (node (ref "J1") (pin "1") (pinfunction "1_1") (pintype "passive"))
      (node (ref "J2") (pin "1") (pinfunction "1_1") (pintype "passive"))
      (node (ref "J3") (pin "1") (pinfunction "1_1") (pintype "passive"))
      (node (ref "JP1") (pin "7") (pinfunction "7_7") (pintype "passive"))
      (node (ref "JP10") (pin "3") (pinfunction "3_3") (pintype "passive"))
      (node (ref "JP11") (pin "3") (pinfunction "3_3") (pintype "passive"))
      (node (ref "JP14") (pin "1") (pinfunction "1_1") (pintype "passive"))
      (node (ref "JP14") (pin "2") (pinfunction "2_2") (pintype "passive"))
      (node (ref "JP15") (pin "4") (pinfunction "4_4") (pintype "passive"))
      (node (ref "JP15") (pin "5") (pinfunction "5_5") (pintype "passive"))
      (node (ref "JP20") (pin "4") (pinfunction "4_4") (pintype "passive"))
      (node (ref "JP21") (pin "4") (pinfunction "4_4") (pintype "passive"))
      (node (ref "JP23") (pin "1") (pinfunction "1_1") (pintype "passive"))
      (node (ref "JP25") (pin "1") (pinfunction "1_1") (pintype "passive"))
      (node (ref "JP27") (pin "GND") (pinfunction "GND_GND") (pintype "bidirectional"))
      (node (ref "JP29") (pin "2") (pinfunction "2_2") (pintype "passive"))
      (node (ref "JP30") (pin "2") (pinfunction "2_2") (pintype "passive"))
      (node (ref "JP31") (pin "3") (pinfunction "3_3") (pintype "passive"))
      (node (ref "JP7") (pin "3") (pinfunction "3_3") (pintype "passive"))
      (node (ref "JP8") (pin "3") (pinfunction "3_3") (pintype "passive"))
      (node (ref "JP9") (pin "3") (pinfunction "3_3") (pintype "passive"))
      (node (ref "LED3") (pin "C") (pinfunction "C_C") (pintype "passive"))
      (node (ref "LED4") (pin "C") (pinfunction "C_C") (pintype "passive"))
      (node (ref "M1") (pin "1") (pinfunction "S1_1") (pintype "bidirectional"))
      (node (ref "M1") (pin "3") (pinfunction "S2_3") (pintype "bidirectional"))
      (node (ref "M2") (pin "1") (pinfunction "S1_1") (pintype "bidirectional"))
      (node (ref "R12") (pin "1") (pinfunction "1_1") (pintype "passive"))
      (node (ref "R13") (pin "1") (pinfunction "1_1") (pintype "passive"))
      (node (ref "R14") (pin "1") (pinfunction "1_1") (pintype "passive"))
      (node (ref "R16") (pin "1") (pinfunction "1_1") (pintype "passive"))
      (node (ref "R2") (pin "1") (pinfunction "1_1") (pintype "passive"))
      (node (ref "R6") (pin "2") (pinfunction "2_2") (pintype "passive"))
      (node (ref "S1") (pin "1") (pinfunction "1_1") (pintype "passive"))
      (node (ref "S1") (pin "2") (pinfunction "2_2") (pintype "passive"))
      (node (ref "U$1") (pin "18") (pinfunction "GND2_18") (pintype "bidirectional"))
      (node (ref "U$1") (pin "21") (pinfunction "GND3_21") (pintype "bidirectional"))
      (node (ref "U$1") (pin "25") (pinfunction "AGND_25") (pintype "bidirectional"))
      (node (ref "U$1") (pin "26") (pinfunction "TEST_26") (pintype "bidirectional"))
      (node (ref "U$1") (pin "7") (pinfunction "GND_7") (pintype "bidirectional"))
      (node (ref "U$2") (pin "2") (pinfunction "VSS_2") (pintype "bidirectional"))
      (node (ref "U$3") (pin "3") (pinfunction "GND_3") (pintype "bidirectional"))
      (node (ref "U1") (pin "1") (pinfunction "ADDR_1") (pintype "input"))
      (node (ref "U2") (pin "3") (pinfunction "GND_3") (pintype "passive"))
    )
    (net (code "86") (name "Net-(D1-3C)") (class "Default")
      (node (ref "D1") (pin "16") (pinfunction "3C_16") (pintype "bidirectional"))
      (node (ref "JP6") (pin "3") (pinfunction "3_3") (pintype "passive"))
    )
    (net (code "87") (name "Net-(D1-4C)") (class "Default")
      (node (ref "D1") (pin "15") (pinfunction "4C_15") (pintype "bidirectional"))
      (node (ref "JP6") (pin "4") (pinfunction "4_4") (pintype "passive"))
    )
    (net (code "88") (name "Net-(D1-5C)") (class "Default")
      (node (ref "D1") (pin "14") (pinfunction "5C_14") (pintype "bidirectional"))
      (node (ref "JP6") (pin "5") (pinfunction "5_5") (pintype "passive"))
    )
    (net (code "89") (name "Net-(D1-6C)") (class "Default")
      (node (ref "D1") (pin "13") (pinfunction "6C_13") (pintype "bidirectional"))
      (node (ref "JP6") (pin "6") (pinfunction "6_6") (pintype "passive"))
    )
    (net (code "90") (name "Net-(D1-7C)") (class "Default")
      (node (ref "D1") (pin "12") (pinfunction "7C_12") (pintype "bidirectional"))
      (node (ref "JP6") (pin "7") (pinfunction "7_7") (pintype "passive"))
    )
    (net (code "91") (name "Net-(D1-8C)") (class "Default")
      (node (ref "D1") (pin "11") (pinfunction "8C_11") (pintype "bidirectional"))
      (node (ref "JP6") (pin "8") (pinfunction "8_8") (pintype "passive"))
    )
    (net (code "92") (name "Net-(D2-1C)") (class "Default")
      (node (ref "D2") (pin "18") (pinfunction "1C_18") (pintype "bidirectional"))
      (node (ref "JP5") (pin "1") (pinfunction "1_1") (pintype "passive"))
    )
    (net (code "93") (name "Net-(D2-2C)") (class "Default")
      (node (ref "D2") (pin "17") (pinfunction "2C_17") (pintype "bidirectional"))
      (node (ref "JP5") (pin "2") (pinfunction "2_2") (pintype "passive"))
    )
    (net (code "94") (name "Net-(D2-3C)") (class "Default")
      (node (ref "D2") (pin "16") (pinfunction "3C_16") (pintype "bidirectional"))
      (node (ref "JP5") (pin "3") (pinfunction "3_3") (pintype "passive"))
    )
    (net (code "95") (name "Net-(D2-4C)") (class "Default")
      (node (ref "D2") (pin "15") (pinfunction "4C_15") (pintype "bidirectional"))
      (node (ref "JP5") (pin "4") (pinfunction "4_4") (pintype "passive"))
    )
    (net (code "96") (name "Net-(D2-5C)") (class "Default")
      (node (ref "D2") (pin "14") (pinfunction "5C_14") (pintype "bidirectional"))
      (node (ref "JP5") (pin "5") (pinfunction "5_5") (pintype "passive"))
    )
    (net (code "97") (name "Net-(D2-6C)") (class "Default")
      (node (ref "D2") (pin "13") (pinfunction "6C_13") (pintype "bidirectional"))
      (node (ref "JP5") (pin "6") (pinfunction "6_6") (pintype "passive"))
    )
    (net (code "98") (name "Net-(D2-7C)") (class "Default")
      (node (ref "D2") (pin "12") (pinfunction "7C_12") (pintype "bidirectional"))
      (node (ref "JP5") (pin "7") (pinfunction "7_7") (pintype "passive"))
    )
    (net (code "99") (name "Net-(D2-8C)") (class "Default")
      (node (ref "D2") (pin "11") (pinfunction "8C_11") (pintype "bidirectional"))
      (node (ref "JP5") (pin "8") (pinfunction "8_8") (pintype "passive"))
    )
    (net (code "100") (name "Net-(JP27-PadVBUS)") (class "Default")
      (node (ref "JP27") (pin "VBUS") (pinfunction "VBUS_VBUS") (pintype "bidirectional"))
      (node (ref "R10") (pin "1") (pinfunction "1_1") (pintype "passive"))
    )
    (net (code "101") (name "Net-(LED1-PadC)") (class "Default")
      (node (ref "LED1") (pin "C") (pinfunction "C_C") (pintype "passive"))
      (node (ref "R14") (pin "2") (pinfunction "2_2") (pintype "passive"))
    )
    (net (code "102") (name "Net-(LED2-PadC)") (class "Default")
      (node (ref "LED2") (pin "C") (pinfunction "C_C") (pintype "passive"))
      (node (ref "R13") (pin "2") (pinfunction "2_2") (pintype "passive"))
    )
    (net (code "103") (name "Net-(LED3-PadA)") (class "Default")
      (node (ref "LED3") (pin "A") (pinfunction "A_A") (pintype "passive"))
      (node (ref "R8") (pin "1") (pinfunction "1_1") (pintype "passive"))
    )
    (net (code "104") (name "Net-(LED4-PadA)") (class "Default")
      (node (ref "LED4") (pin "A") (pinfunction "A_A") (pintype "passive"))
      (node (ref "R7") (pin "1") (pinfunction "1_1") (pintype "passive"))
    )
    (net (code "105") (name "Net-(LED5-PadC)") (class "Default")
      (node (ref "LED5") (pin "C") (pinfunction "C_C") (pintype "passive"))
      (node (ref "R12") (pin "2") (pinfunction "2_2") (pintype "passive"))
    )
    (net (code "106") (name "Net-(LED6-PadC)") (class "Default")
      (node (ref "LED6") (pin "C") (pinfunction "C_C") (pintype "passive"))
      (node (ref "R18") (pin "2") (pinfunction "2_2") (pintype "passive"))
    )
    (net (code "107") (name "Net-(LED7-PadC)") (class "Default")
      (node (ref "LED7") (pin "C") (pinfunction "C_C") (pintype "passive"))
      (node (ref "R17") (pin "2") (pinfunction "2_2") (pintype "passive"))
    )
    (net (code "108") (name "Net-(M1-D1_B)") (class "Default")
      (node (ref "JP26") (pin "2") (pinfunction "2_2") (pintype "passive"))
      (node (ref "M1") (pin "7") (pinfunction "D1_B_7") (pintype "bidirectional"))
    )
    (net (code "109") (name "Net-(M1-D2_A)") (class "Default")
      (node (ref "JP26") (pin "3") (pinfunction "3_3") (pintype "passive"))
      (node (ref "M1") (pin "6") (pinfunction "D2_A_6") (pintype "bidirectional"))
    )
    (net (code "110") (name "Net-(M2-D1_A)") (class "Default")
      (node (ref "JP26") (pin "4") (pinfunction "4_4") (pintype "passive"))
      (node (ref "M2") (pin "8") (pinfunction "D1_A_8") (pintype "bidirectional"))
    )
    (net (code "111") (name "Net-(U$1-3V3OUT)") (class "Default")
      (node (ref "C7") (pin "2") (pinfunction "2_2") (pintype "passive"))
      (node (ref "U$1") (pin "17") (pinfunction "3V3OUT_17") (pintype "bidirectional"))
    )
    (net (code "112") (name "Net-(U$1-RESET#)") (class "Default")
      (node (ref "R10") (pin "2") (pinfunction "2_2") (pintype "passive"))
      (node (ref "R6") (pin "1") (pinfunction "1_1") (pintype "passive"))
      (node (ref "U$1") (pin "19") (pinfunction "RESET#_19") (pintype "bidirectional"))
    )
    (net (code "113") (name "Net-(U$2-VCORE)") (class "Default")
      (node (ref "C2") (pin "1") (pinfunction "1_1") (pintype "passive"))
      (node (ref "U$2") (pin "1") (pinfunction "VCORE_1") (pintype "bidirectional"))
    )
    (net (code "114") (name "Net-(U1-AIN0)") (class "Default")
      (node (ref "JP28") (pin "1") (pinfunction "1_1") (pintype "passive"))
      (node (ref "U1") (pin "4") (pinfunction "AIN0_4") (pintype "input"))
    )
    (net (code "115") (name "Net-(U1-ALERT{slash}RDY)") (class "Default")
      (node (ref "R11") (pin "1") (pinfunction "1_1") (pintype "passive"))
      (node (ref "U1") (pin "2") (pinfunction "ALERT/RDY_2") (pintype "input"))
    )
    (net (code "116") (name "Net-(U1-GND)") (class "Default")
      (node (ref "B1") (pin "1") (pinfunction "1_1") (pintype "passive"))
      (node (ref "U1") (pin "3") (pinfunction "GND_3") (pintype "passive"))
    )
    (net (code "117") (name "Net-(U1-VDD)") (class "Default")
      (node (ref "B2") (pin "2") (pinfunction "2_2") (pintype "passive"))
      (node (ref "U1") (pin "8") (pinfunction "VDD_8") (pintype "power_in"))
    )
    (net (code "118") (name "Net-(U2-ADDR)") (class "Default")
      (node (ref "R19") (pin "1") (pinfunction "1_1") (pintype "passive"))
      (node (ref "U2") (pin "1") (pinfunction "ADDR_1") (pintype "input"))
    )
    (net (code "119") (name "Net-(U2-ALERT{slash}RDY)") (class "Default")
      (node (ref "R15") (pin "1") (pinfunction "1_1") (pintype "passive"))
      (node (ref "U2") (pin "2") (pinfunction "ALERT/RDY_2") (pintype "input"))
    )
    (net (code "120") (name "unconnected-(D1-1B-Pad1)") (class "Default")
      (node (ref "D1") (pin "1") (pinfunction "1B_1") (pintype "bidirectional"))
    )
    (net (code "121") (name "unconnected-(D1-1C-Pad18)") (class "Default")
      (node (ref "D1") (pin "18") (pinfunction "1C_18") (pintype "bidirectional"))
    )
    (net (code "122") (name "unconnected-(D1-2B-Pad2)") (class "Default")
      (node (ref "D1") (pin "2") (pinfunction "2B_2") (pintype "bidirectional"))
    )
    (net (code "123") (name "unconnected-(D1-2C-Pad17)") (class "Default")
      (node (ref "D1") (pin "17") (pinfunction "2C_17") (pintype "bidirectional"))
    )
    (net (code "124") (name "unconnected-(JP6-Pad2)") (class "Default")
      (node (ref "JP6") (pin "2") (pinfunction "2_2") (pintype "passive"))
    )
    (net (code "125") (name "unconnected-(JP10-Pad2)") (class "Default")
      (node (ref "JP10") (pin "2") (pinfunction "2_2") (pintype "passive"))
    )
    (net (code "126") (name "unconnected-(JP11-Pad2)") (class "Default")
      (node (ref "JP11") (pin "2") (pinfunction "2_2") (pintype "passive"))
    )
    (net (code "127") (name "unconnected-(M1-D1_A-Pad8)") (class "Default")
      (node (ref "M1") (pin "8") (pinfunction "D1_A_8") (pintype "bidirectional"))
    )
    (net (code "128") (name "unconnected-(M1-D2_B-Pad5)") (class "Default")
      (node (ref "M1") (pin "5") (pinfunction "D2_B_5") (pintype "bidirectional"))
    )
    (net (code "129") (name "unconnected-(M2-D1_B-Pad7)") (class "Default")
      (node (ref "M2") (pin "7") (pinfunction "D1_B_7") (pintype "bidirectional"))
    )
    (net (code "130") (name "unconnected-(M2-D2_A-Pad6)") (class "Default")
      (node (ref "M2") (pin "6") (pinfunction "D2_A_6") (pintype "bidirectional"))
    )
    (net (code "131") (name "unconnected-(M2-D2_B-Pad5)") (class "Default")
      (node (ref "M2") (pin "5") (pinfunction "D2_B_5") (pintype "bidirectional"))
    )
    (net (code "132") (name "unconnected-(M2-G2-Pad4)") (class "Default")
      (node (ref "M2") (pin "4") (pinfunction "G2_4") (pintype "bidirectional"))
    )
    (net (code "133") (name "unconnected-(M2-S2-Pad3)") (class "Default")
      (node (ref "M2") (pin "3") (pinfunction "S2_3") (pintype "bidirectional"))
    )
    (net (code "134") (name "unconnected-(U$1-CBUS2-Pad13)") (class "Default")
      (node (ref "U$1") (pin "13") (pinfunction "CBUS2_13") (pintype "bidirectional"))
    )
    (net (code "135") (name "unconnected-(U$1-CBUS3-Pad14)") (class "Default")
      (node (ref "U$1") (pin "14") (pinfunction "CBUS3_14") (pintype "bidirectional"))
    )
    (net (code "136") (name "unconnected-(U$1-CBUS4-Pad12)") (class "Default")
      (node (ref "U$1") (pin "12") (pinfunction "CBUS4_12") (pintype "bidirectional"))
    )
    (net (code "137") (name "unconnected-(U$1-CTS-Pad11)") (class "Default")
      (node (ref "U$1") (pin "11") (pinfunction "CTS_11") (pintype "bidirectional"))
    )
    (net (code "138") (name "unconnected-(U$1-DCD-Pad10)") (class "Default")
      (node (ref "U$1") (pin "10") (pinfunction "DCD_10") (pintype "bidirectional"))
    )
    (net (code "139") (name "unconnected-(U$1-DSR-Pad9)") (class "Default")
      (node (ref "U$1") (pin "9") (pinfunction "DSR_9") (pintype "bidirectional"))
    )
    (net (code "140") (name "unconnected-(U$1-DTR-Pad2)") (class "Default")
      (node (ref "U$1") (pin "2") (pinfunction "DTR_2") (pintype "bidirectional"))
    )
    (net (code "141") (name "unconnected-(U$1-NC-Pad8)") (class "Default")
      (node (ref "U$1") (pin "8") (pinfunction "NC_8") (pintype "bidirectional"))
    )
    (net (code "142") (name "unconnected-(U$1-NC2-Pad24)") (class "Default")
      (node (ref "U$1") (pin "24") (pinfunction "NC2_24") (pintype "bidirectional"))
    )
    (net (code "143") (name "unconnected-(U$1-OSCI-Pad27)") (class "Default")
      (node (ref "U$1") (pin "27") (pinfunction "OSCI_27") (pintype "bidirectional"))
    )
    (net (code "144") (name "unconnected-(U$1-OSCO-Pad28)") (class "Default")
      (node (ref "U$1") (pin "28") (pinfunction "OSCO_28") (pintype "bidirectional"))
    )
    (net (code "145") (name "unconnected-(U$1-RI-Pad6)") (class "Default")
      (node (ref "U$1") (pin "6") (pinfunction "RI_6") (pintype "bidirectional"))
    )
    (net (code "146") (name "unconnected-(U$1-RTS-Pad3)") (class "Default")
      (node (ref "U$1") (pin "3") (pinfunction "RTS_3") (pintype "bidirectional"))
    )
    (net (code "147") (name "unconnected-(U$2-AL_H-Pad5)") (class "Default")
      (node (ref "U$2") (pin "5") (pinfunction "AL_H_5") (pintype "bidirectional"))
    )
    (net (code "148") (name "unconnected-(U$2-AL_L-Pad6)") (class "Default")
      (node (ref "U$2") (pin "6") (pinfunction "AL_L_6") (pintype "bidirectional"))
    )
    (net (code "149") (name "unconnected-(U$2-NC-Pad7)") (class "Default")
      (node (ref "U$2") (pin "7") (pinfunction "NC_7") (pintype "bidirectional"))
    )
    (net (code "150") (name "unconnected-(U1-AIN1-Pad5)") (class "Default")
      (node (ref "U1") (pin "5") (pinfunction "AIN1_5") (pintype "input"))
    )
    (net (code "151") (name "unconnected-(U1-AIN2-Pad6)") (class "Default")
      (node (ref "U1") (pin "6") (pinfunction "AIN2_6") (pintype "input"))
    )
    (net (code "152") (name "unconnected-(U1-AIN3-Pad7)") (class "Default")
      (node (ref "U1") (pin "7") (pinfunction "AIN3_7") (pintype "input"))
    )
    (net (code "153") (name "unconnected-(U2-AIN2-Pad6)") (class "Default")
      (node (ref "U2") (pin "6") (pinfunction "AIN2_6") (pintype "input"))
    )
    (net (code "154") (name "unconnected-(U2-AIN3-Pad7)") (class "Default")
      (node (ref "U2") (pin "7") (pinfunction "AIN3_7") (pintype "input"))
    )
  )
)
